# PowerBoard.net
KiCad netlist of a schematic drawn in EAGLE
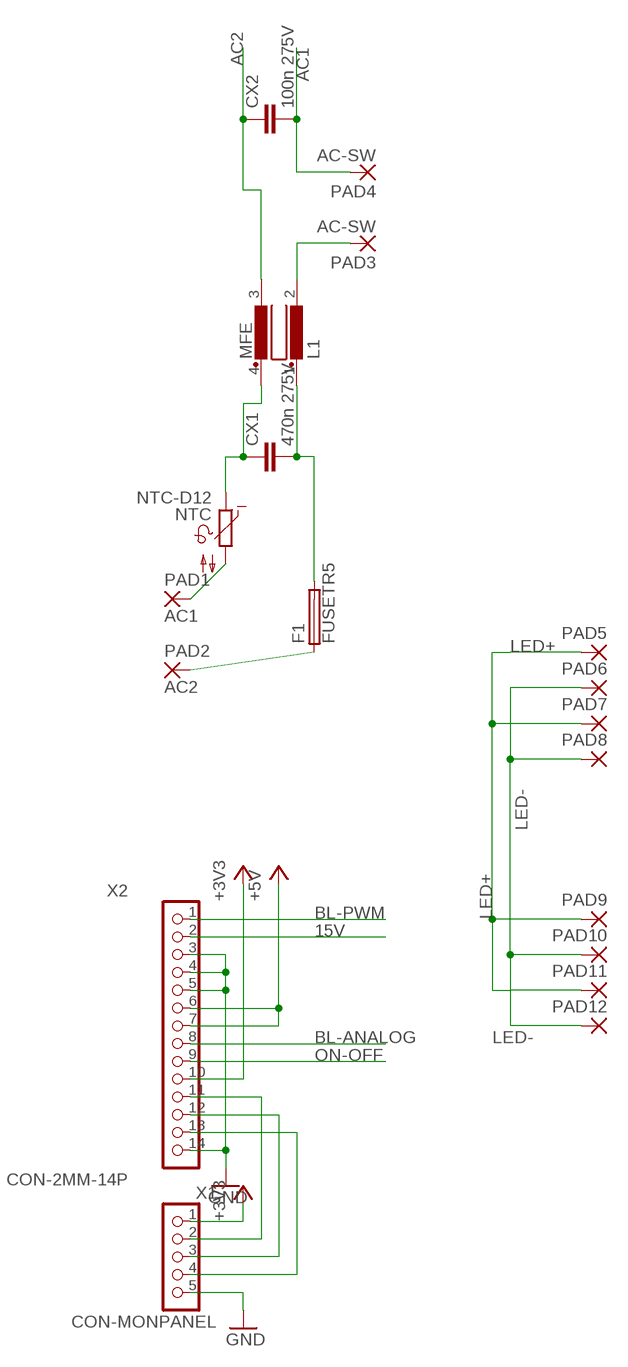
[diagram p0: schematic, sheet 1]
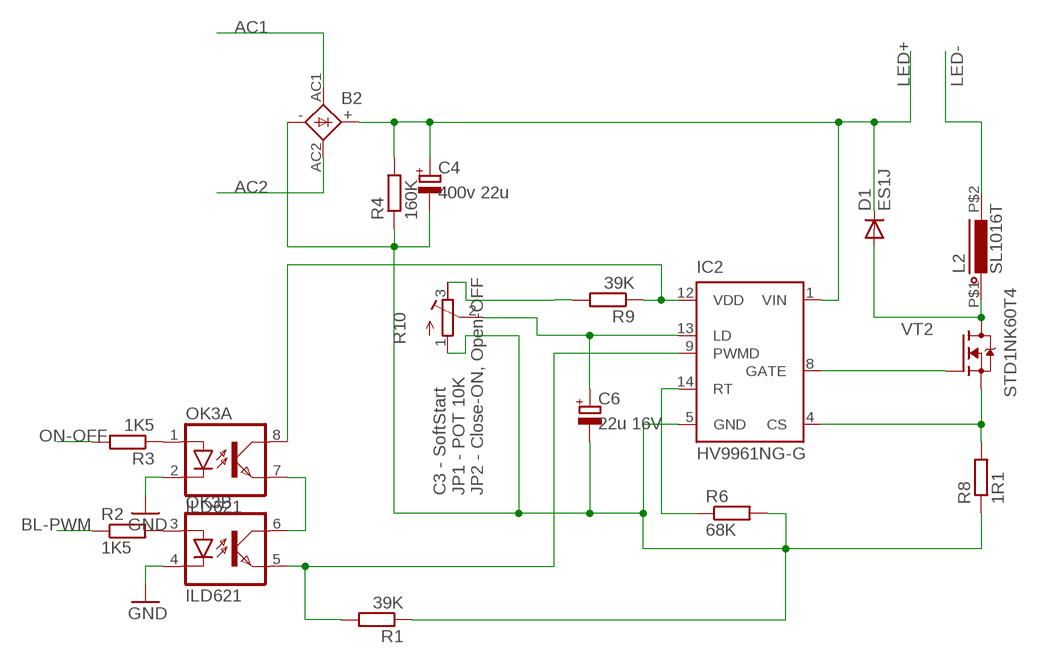
[diagram p1: schematic, sheet 2]
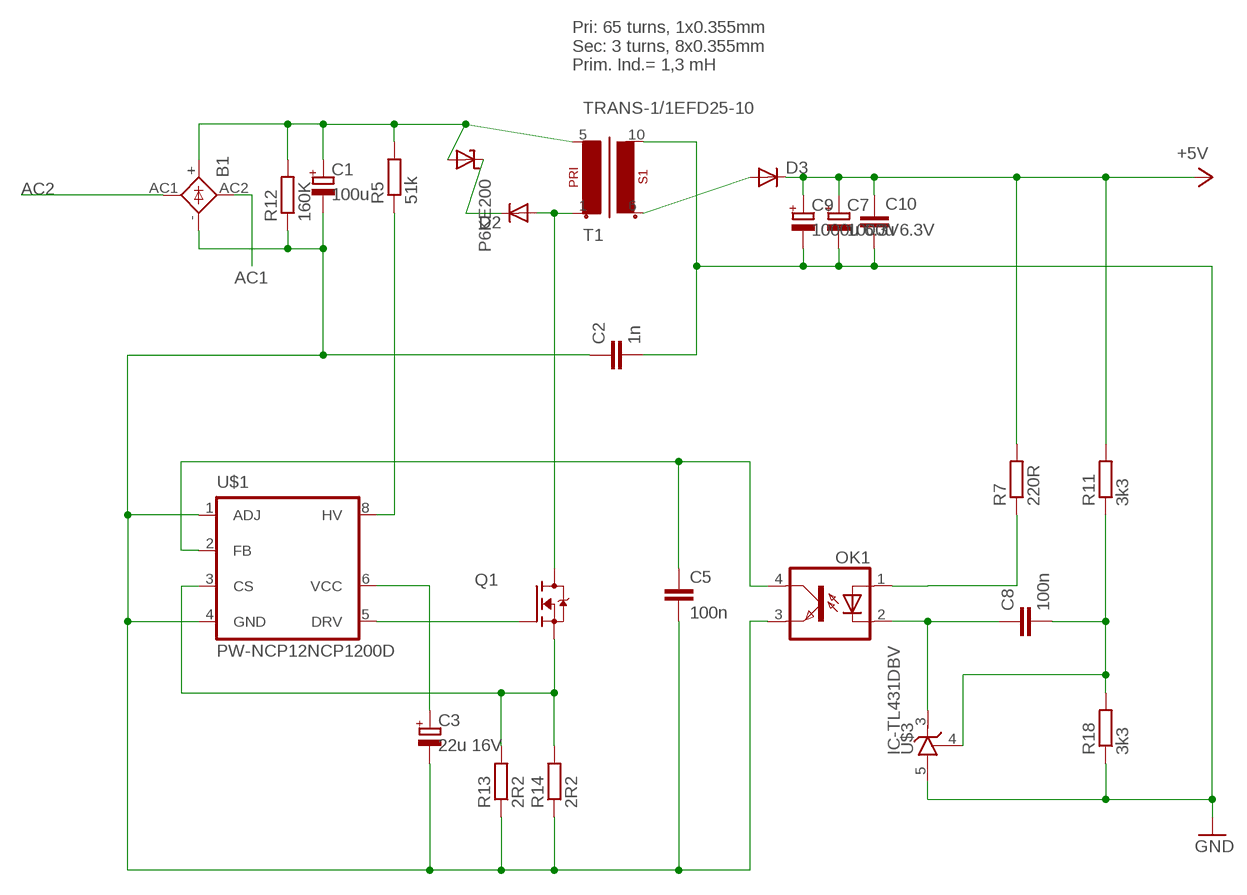
[diagram p2: schematic, sheet 3]

(export (version "E")
  (design (tool "Eeschema 10.0.6"))
  (components
    (comp (ref "B1")
      (value "KBL")
      (footprint "eagle-import:KBL")
      (libsource (lib "eagle-import") (part "KBL"))
    )
    (comp (ref "C1")
      (value "100u")
      (footprint "eagle-import:E5-13-35-HORIZ")
      (libsource (lib "eagle-import") (part "CAP-POL_E5-13-35-H"))
    )
    (comp (ref "C2")
      (value "1n")
      (footprint "eagle-import:C050-024X044")
      (libsource (lib "eagle-import") (part "Namenlos_CAP_C50-024X044"))
    )
    (comp (ref "C3")
      (value "22u 16V")
      (footprint "eagle-import:E2,5-7")
      (libsource (lib "eagle-import") (part "Namenlos_CAP-POL_E2.5-7"))
    )
    (comp (ref "C5")
      (value "100n")
      (footprint "eagle-import:CAP1206")
      (libsource (lib "eagle-import") (part "CAP_1206"))
    )
    (comp (ref "C7")
      (value "1000u 6.3V")
      (footprint "eagle-import:E3,5-8")
      (libsource (lib "eagle-import") (part "CAP-POL_E3.5-8"))
    )
    (comp (ref "C8")
      (value "100n")
      (footprint "eagle-import:CAP1206")
      (libsource (lib "eagle-import") (part "CAP_1206"))
    )
    (comp (ref "C9")
      (value "1000u 6.3V")
      (footprint "eagle-import:E3,5-8")
      (libsource (lib "eagle-import") (part "CAP-POL_E3.5-8"))
    )
    (comp (ref "C10")
      (value "CAP_0805")
      (footprint "eagle-import:CAP0805")
      (libsource (lib "eagle-import") (part "CAP_0805"))
    )
    (comp (ref "D2")
      (value "DIODE_ES1J")
      (footprint "eagle-import:DO214AC")
      (libsource (lib "eagle-import") (part "DIODE_ES1J"))
    )
    (comp (ref "D3")
      (value "DIODE_TO-220-2")
      (footprint "eagle-import:TO220ACS")
      (libsource (lib "eagle-import") (part "DIODE_TO-220-2"))
    )
    (comp (ref "OK1")
      (value "OPTOTRANSPC817")
      (footprint "eagle-import:DIL04")
      (fields (field (name "MPN") "PC817X4J000F"))
      (libsource (lib "eagle-import") (part "OPTOTRANSPC817"))
    )
    (comp (ref "P6KE200")
      (value "SUPRESSORDO-204AC")
      (footprint "eagle-import:DO15-12")
      (libsource (lib "eagle-import") (part "SUPRESSORDO-204AC"))
    )
    (comp (ref "Q1")
      (value "FET-NTO-220")
      (footprint "eagle-import:TO-220V")
      (libsource (lib "eagle-import") (part "FET-NTO-220"))
    )
    (comp (ref "R5")
      (value "51k")
      (footprint "eagle-import:SQP-5")
      (libsource (lib "eagle-import") (part "R_SQP-5"))
    )
    (comp (ref "R7")
      (value "220R")
      (footprint "eagle-import:RESC3216X60")
      (libsource (lib "eagle-import") (part "R_R1206"))
    )
    (comp (ref "R11")
      (value "3k3")
      (footprint "eagle-import:RESC3216X60")
      (libsource (lib "eagle-import") (part "R_R1206"))
    )
    (comp (ref "R12")
      (value "160K")
      (footprint "eagle-import:MF-0125")
      (libsource (lib "eagle-import") (part "Namenlos_R_MF-0125"))
    )
    (comp (ref "R13")
      (value "2R2")
      (footprint "eagle-import:MF-025")
      (libsource (lib "eagle-import") (part "R_MF-025"))
    )
    (comp (ref "R14")
      (value "2R2")
      (footprint "eagle-import:MF-025")
      (libsource (lib "eagle-import") (part "R_MF-025"))
    )
    (comp (ref "R18")
      (value "3k3")
      (footprint "eagle-import:RESC3216X60")
      (libsource (lib "eagle-import") (part "R_R1206"))
    )
    (comp (ref "T1")
      (value "TRANS-1/1EFD25-10")
      (footprint "eagle-import:EFD25_10PIN")
      (libsource (lib "eagle-import") (part "TRANS-1/1EFD25-10"))
    )
    (comp (ref "U$1")
      (value "PW-NCP12NCP1200D")
      (footprint "eagle-import:SO8")
      (libsource (lib "eagle-import") (part "PW-NCP12NCP1200D"))
    )
    (comp (ref "U$3")
      (value "IC-TL431DBV")
      (footprint "eagle-import:SOT95P280X145-5")
      (libsource (lib "eagle-import") (part "IC-TL431DBV"))
    )
    (comp (ref "CX1")
      (value "470n 275V")
      (footprint "eagle-import:XC15B10")
      (libsource (lib "eagle-import") (part "CXXC15B10"))
    )
    (comp (ref "CX2")
      (value "100n 275V")
      (footprint "eagle-import:XC15B6")
      (libsource (lib "eagle-import") (part "CXXC15B6"))
    )
    (comp (ref "F1")
      (value "FUSETR5")
      (footprint "eagle-import:TR5")
      (libsource (lib "eagle-import") (part "FUSETR5"))
    )
    (comp (ref "L1")
      (value "MFE")
      (footprint "eagle-import:MFE")
      (libsource (lib "eagle-import") (part "MFE"))
    )
    (comp (ref "NTC")
      (value "NTC-D12")
      (footprint "eagle-import:NTC-D12")
      (libsource (lib "eagle-import") (part "NTC-D12"))
    )
    (comp (ref "PAD1")
      (value "AC1")
      (footprint "eagle-import:3,81_1,4")
      (libsource (lib "eagle-import") (part "WIREPAD3,81/1,4"))
    )
    (comp (ref "PAD2")
      (value "AC2")
      (footprint "eagle-import:3,81_1,4")
      (libsource (lib "eagle-import") (part "WIREPAD3,81/1,4"))
    )
    (comp (ref "PAD3")
      (value "AC-SW")
      (footprint "eagle-import:2,54_1,1")
      (libsource (lib "eagle-import") (part "WIREPAD2,54/1,1"))
    )
    (comp (ref "PAD4")
      (value "AC-SW")
      (footprint "eagle-import:2,54_1,1")
      (libsource (lib "eagle-import") (part "WIREPAD2,54/1,1"))
    )
    (comp (ref "PAD5")
      (value "2,54/1,1")
      (footprint "eagle-import:2,54_1,1")
      (libsource (lib "eagle-import") (part "2,54/1,1"))
    )
    (comp (ref "PAD6")
      (value "2,54/1,1")
      (footprint "eagle-import:2,54_1,1")
      (libsource (lib "eagle-import") (part "2,54/1,1"))
    )
    (comp (ref "PAD7")
      (value "2,54/1,1")
      (footprint "eagle-import:2,54_1,1")
      (libsource (lib "eagle-import") (part "2,54/1,1"))
    )
    (comp (ref "PAD8")
      (value "2,54/1,1")
      (footprint "eagle-import:2,54_1,1")
      (libsource (lib "eagle-import") (part "2,54/1,1"))
    )
    (comp (ref "PAD9")
      (value "2,54/1,1")
      (footprint "eagle-import:2,54_1,1")
      (libsource (lib "eagle-import") (part "2,54/1,1"))
    )
    (comp (ref "PAD10")
      (value "2,54/1,1")
      (footprint "eagle-import:2,54_1,1")
      (libsource (lib "eagle-import") (part "2,54/1,1"))
    )
    (comp (ref "PAD11")
      (value "2,54/1,1")
      (footprint "eagle-import:2,54_1,1")
      (libsource (lib "eagle-import") (part "2,54/1,1"))
    )
    (comp (ref "PAD12")
      (value "2,54/1,1")
      (footprint "eagle-import:2,54_1,1")
      (libsource (lib "eagle-import") (part "2,54/1,1"))
    )
    (comp (ref "X1")
      (value "CON-MONPANEL")
      (footprint "eagle-import:CON-5-PANEL")
      (libsource (lib "eagle-import") (part "CON-MONPANEL"))
    )
    (comp (ref "X2")
      (value "CON-2MM-14P")
      (footprint "eagle-import:CON-14-2MM")
      (libsource (lib "eagle-import") (part "CON-2MM-14P"))
    )
    (comp (ref "B2")
      (value "BRIDGEDBS")
      (footprint "eagle-import:DBS")
      (libsource (lib "eagle-import") (part "BRIDGEDBS"))
    )
    (comp (ref "C4")
      (value "400v 22u")
      (footprint "eagle-import:E3,5-8")
      (libsource (lib "eagle-import") (part "Namenlos_CAP-POL_E3.5-8"))
    )
    (comp (ref "C6")
      (value "22u 16V")
      (footprint "eagle-import:CT3528")
      (libsource (lib "eagle-import") (part "CAP-POL_3528"))
    )
    (comp (ref "D1")
      (value "ES1J")
      (footprint "eagle-import:DO214AC")
      (libsource (lib "eagle-import") (part "DIODE_ES1J"))
    )
    (comp (ref "IC2")
      (value "HV9961NG-G")
      (footprint "eagle-import:SOIC-16NG")
      (libsource (lib "eagle-import") (part "HV9910BNG"))
    )
    (comp (ref "L2")
      (value "SL1016T")
      (footprint "eagle-import:SL1016")
      (libsource (lib "eagle-import") (part "INDUCTORSL1016"))
    )
    (comp (ref "OK3")
      (value "ILD621")
      (footprint "eagle-import:DIL08")
      (fields (field (name "MF") "VISHAY/TELEFUNKEN"))
      (libsource (lib "eagle-import") (part "ILD621"))
    )
    (comp (ref "R1")
      (value "39K")
      (footprint "eagle-import:RESC2012X50")
      (libsource (lib "eagle-import") (part "R_R0805"))
    )
    (comp (ref "R2")
      (value "1K5")
      (footprint "eagle-import:MF-025")
      (libsource (lib "eagle-import") (part "R_MF-025"))
    )
    (comp (ref "R3")
      (value "1K5")
      (footprint "eagle-import:MF-025")
      (libsource (lib "eagle-import") (part "R_MF-025"))
    )
    (comp (ref "R4")
      (value "160K")
      (footprint "eagle-import:MF-0125")
      (libsource (lib "eagle-import") (part "R_MF-0125"))
    )
    (comp (ref "R6")
      (value "68K")
      (footprint "eagle-import:RESC2012X50")
      (libsource (lib "eagle-import") (part "R_R0805"))
    )
    (comp (ref "R8")
      (value "1R1")
      (footprint "eagle-import:MF-05")
      (libsource (lib "eagle-import") (part "R_MF-05"))
    )
    (comp (ref "R9")
      (value "39K")
      (footprint "eagle-import:RESC2012X50")
      (libsource (lib "eagle-import") (part "R_R0805"))
    )
    (comp (ref "R10")
      (value "R_POT3296X")
      (footprint "eagle-import:POT-3296X")
      (libsource (lib "eagle-import") (part "R_POT3296X"))
    )
    (comp (ref "VT2")
      (value "STD1NK60T4")
      (footprint "eagle-import:DPAK")
      (libsource (lib "eagle-import") (part "FET-NDPAK"))
    )
  )
  (nets
    (net (code "1") (name "+3V3") (class "Default")
      (node (ref "X1") (pin "1") (pinfunction "1_1") (pintype "passive"))
      (node (ref "X2") (pin "10") (pinfunction "10_10") (pintype "passive"))
    )
    (net (code "2") (name "+5V") (class "Default")
      (node (ref "C10") (pin "1") (pinfunction "1_1") (pintype "passive"))
      (node (ref "C7") (pin "+") (pinfunction "+_+") (pintype "passive"))
      (node (ref "C9") (pin "+") (pinfunction "+_+") (pintype "passive"))
      (node (ref "D3") (pin "C") (pinfunction "C_C") (pintype "passive"))
      (node (ref "R11") (pin "2") (pinfunction "2_2") (pintype "passive"))
      (node (ref "R7") (pin "2") (pinfunction "2_2") (pintype "passive"))
      (node (ref "X2") (pin "6") (pinfunction "6_6") (pintype "passive"))
      (node (ref "X2") (pin "7") (pinfunction "7_7") (pintype "passive"))
    )
    (net (code "3") (name "15V") (class "Default")
      (node (ref "X2") (pin "2") (pinfunction "2_2") (pintype "passive"))
    )
    (net (code "4") (name "AC1") (class "Default")
      (node (ref "B1") (pin "AC2") (pinfunction "AC1_AC2") (pintype "passive"))
      (node (ref "B2") (pin "AC1") (pinfunction "AC1_AC1") (pintype "passive"))
      (node (ref "CX2") (pin "2") (pinfunction "2_2") (pintype "passive"))
      (node (ref "PAD4") (pin "1") (pinfunction "P_1") (pintype "passive"))
    )
    (net (code "5") (name "AC2") (class "Default")
      (node (ref "B1") (pin "AC1") (pinfunction "AC2_AC1") (pintype "passive"))
      (node (ref "B2") (pin "AC2") (pinfunction "AC2_AC2") (pintype "passive"))
      (node (ref "CX2") (pin "1") (pinfunction "1_1") (pintype "passive"))
      (node (ref "L1") (pin "3") (pinfunction "4_3") (pintype "passive"))
    )
    (net (code "6") (name "BL-ANALOG") (class "Default")
      (node (ref "X2") (pin "8") (pinfunction "8_8") (pintype "passive"))
    )
    (net (code "7") (name "BL-PWM") (class "Default")
      (node (ref "R2") (pin "1") (pinfunction "1_1") (pintype "passive"))
      (node (ref "X2") (pin "1") (pinfunction "1_1") (pintype "passive"))
    )
    (net (code "8") (name "GND") (class "Default")
      (node (ref "C10") (pin "2") (pinfunction "2_2") (pintype "passive"))
      (node (ref "C2") (pin "2") (pinfunction "2_2") (pintype "passive"))
      (node (ref "C7") (pin "-") (pinfunction "-_-") (pintype "passive"))
      (node (ref "C9") (pin "-") (pinfunction "-_-") (pintype "passive"))
      (node (ref "OK3") (pin "2") (pinfunction "C_2") (pintype "passive"))
      (node (ref "OK3") (pin "4") (pinfunction "C_4") (pintype "passive"))
      (node (ref "R18") (pin "1") (pinfunction "1_1") (pintype "passive"))
      (node (ref "T1") (pin "10") (pinfunction "S1-2_10") (pintype "passive"))
      (node (ref "U$3") (pin "5") (pinfunction "A_5") (pintype "passive"))
      (node (ref "X1") (pin "5") (pinfunction "5_5") (pintype "passive"))
      (node (ref "X2") (pin "14") (pinfunction "14_14") (pintype "passive"))
      (node (ref "X2") (pin "3") (pinfunction "3_3") (pintype "passive"))
      (node (ref "X2") (pin "4") (pinfunction "4_4") (pintype "passive"))
      (node (ref "X2") (pin "5") (pinfunction "5_5") (pintype "passive"))
    )
    (net (code "9") (name "LED+") (class "Default")
      (node (ref "B2") (pin "+") (pinfunction "+_+") (pintype "passive"))
      (node (ref "C4") (pin "+") (pinfunction "+_+") (pintype "passive"))
      (node (ref "D1") (pin "C") (pinfunction "C_C") (pintype "passive"))
      (node (ref "IC2") (pin "1") (pinfunction "VIN_1") (pintype "input"))
      (node (ref "PAD11") (pin "1") (pinfunction "P_1") (pintype "passive"))
      (node (ref "PAD5") (pin "1") (pinfunction "P_1") (pintype "passive"))
      (node (ref "PAD7") (pin "1") (pinfunction "P_1") (pintype "passive"))
      (node (ref "PAD9") (pin "1") (pinfunction "P_1") (pintype "passive"))
      (node (ref "R4") (pin "2") (pinfunction "2_2") (pintype "passive"))
    )
    (net (code "10") (name "LED-") (class "Default")
      (node (ref "L2") (pin "P$2") (pinfunction "2_P$2") (pintype "passive"))
      (node (ref "PAD10") (pin "1") (pinfunction "P_1") (pintype "passive"))
      (node (ref "PAD12") (pin "1") (pinfunction "P_1") (pintype "passive"))
      (node (ref "PAD6") (pin "1") (pinfunction "P_1") (pintype "passive"))
      (node (ref "PAD8") (pin "1") (pinfunction "P_1") (pintype "passive"))
    )
    (net (code "11") (name "Net-(CX1-Pad2)") (class "Default")
      (node (ref "CX1") (pin "2") (pinfunction "2_2") (pintype "passive"))
      (node (ref "F1") (pin "2") (pinfunction "2_2") (pintype "passive"))
      (node (ref "L1") (pin "1") (pinfunction "1_1") (pintype "passive"))
    )
    (net (code "12") (name "Net-(D2-PadC)") (class "Default")
      (node (ref "D2") (pin "C") (pinfunction "C_C") (pintype "passive"))
      (node (ref "P6KE200") (pin "C") (pinfunction "C_C") (pintype "passive"))
    )
    (net (code "13") (name "Net-(IC2-CS)") (class "Default")
      (node (ref "IC2") (pin "4") (pinfunction "CS_4") (pintype "input"))
      (node (ref "R8") (pin "2") (pinfunction "2_2") (pintype "passive"))
      (node (ref "VT2") (pin "S") (pinfunction "S_S") (pintype "passive"))
    )
    (net (code "14") (name "Net-(IC2-GATE)") (class "Default")
      (node (ref "IC2") (pin "8") (pinfunction "GATE_8") (pintype "output"))
      (node (ref "VT2") (pin "G") (pinfunction "G_G") (pintype "passive"))
    )
    (net (code "15") (name "Net-(IC2-GND)") (class "Default")
      (node (ref "B2") (pin "-") (pinfunction "-_-") (pintype "passive"))
      (node (ref "C4") (pin "-") (pinfunction "-_-") (pintype "passive"))
      (node (ref "C6") (pin "-") (pinfunction "-_-") (pintype "passive"))
      (node (ref "IC2") (pin "5") (pinfunction "GND_5") (pintype "power_in"))
      (node (ref "R1") (pin "1") (pinfunction "1_1") (pintype "passive"))
      (node (ref "R10") (pin "1") (pinfunction "A_1") (pintype "passive"))
      (node (ref "R4") (pin "1") (pinfunction "1_1") (pintype "passive"))
      (node (ref "R6") (pin "2") (pinfunction "2_2") (pintype "passive"))
      (node (ref "R8") (pin "1") (pinfunction "1_1") (pintype "passive"))
    )
    (net (code "16") (name "Net-(IC2-LD)") (class "Default")
      (node (ref "C6") (pin "+") (pinfunction "+_+") (pintype "passive"))
      (node (ref "IC2") (pin "13") (pinfunction "LD_13") (pintype "input"))
      (node (ref "R10") (pin "2") (pinfunction "S_2") (pintype "passive"))
    )
    (net (code "17") (name "Net-(IC2-PWMD)") (class "Default")
      (node (ref "IC2") (pin "9") (pinfunction "PWMD_9") (pintype "input"))
      (node (ref "OK3") (pin "5") (pinfunction "EMIT_5") (pintype "passive"))
      (node (ref "R1") (pin "2") (pinfunction "2_2") (pintype "passive"))
    )
    (net (code "18") (name "Net-(IC2-RT)") (class "Default")
      (node (ref "IC2") (pin "14") (pinfunction "RT_14") (pintype "passive"))
      (node (ref "R6") (pin "1") (pinfunction "1_1") (pintype "passive"))
    )
    (net (code "19") (name "Net-(IC2-VDD)") (class "Default")
      (node (ref "IC2") (pin "12") (pinfunction "VDD_12") (pintype "power_in"))
      (node (ref "OK3") (pin "8") (pinfunction "COL_8") (pintype "passive"))
      (node (ref "R9") (pin "1") (pinfunction "1_1") (pintype "passive"))
    )
    (net (code "20") (name "Net-(L1-3)") (class "Default")
      (node (ref "CX1") (pin "1") (pinfunction "1_1") (pintype "passive"))
      (node (ref "L1") (pin "4") (pinfunction "3_4") (pintype "passive"))
      (node (ref "NTC") (pin "1") (pinfunction "1_1") (pintype "passive"))
    )
    (net (code "21") (name "Net-(L2-1)") (class "Default")
      (node (ref "D1") (pin "A") (pinfunction "A_A") (pintype "passive"))
      (node (ref "L2") (pin "P$1") (pinfunction "1_P$1") (pintype "passive"))
      (node (ref "VT2") (pin "D") (pinfunction "D_D") (pintype "passive"))
    )
    (net (code "22") (name "Net-(OK1-A)") (class "Default")
      (node (ref "OK1") (pin "1") (pinfunction "A_1") (pintype "passive"))
      (node (ref "R7") (pin "1") (pinfunction "1_1") (pintype "passive"))
    )
    (net (code "23") (name "Net-(OK1-C)") (class "Default")
      (node (ref "C8") (pin "1") (pinfunction "1_1") (pintype "passive"))
      (node (ref "OK1") (pin "2") (pinfunction "C_2") (pintype "passive"))
      (node (ref "U$3") (pin "3") (pinfunction "C_3") (pintype "passive"))
    )
    (net (code "24") (name "Net-(OK1-COL)") (class "Default")
      (node (ref "C5") (pin "1") (pinfunction "1_1") (pintype "passive"))
      (node (ref "OK1") (pin "4") (pinfunction "COL_4") (pintype "passive"))
      (node (ref "U$1") (pin "2") (pinfunction "FB_2") (pintype "input"))
    )
    (net (code "25") (name "Net-(OK1-EMIT)") (class "Default")
      (node (ref "B1") (pin "-") (pinfunction "-_-") (pintype "passive"))
      (node (ref "C1") (pin "-") (pinfunction "-_-") (pintype "passive"))
      (node (ref "C2") (pin "1") (pinfunction "1_1") (pintype "passive"))
      (node (ref "C3") (pin "-") (pinfunction "-_-") (pintype "passive"))
      (node (ref "C5") (pin "2") (pinfunction "2_2") (pintype "passive"))
      (node (ref "OK1") (pin "3") (pinfunction "EMIT_3") (pintype "passive"))
      (node (ref "R12") (pin "1") (pinfunction "1_1") (pintype "passive"))
      (node (ref "R13") (pin "1") (pinfunction "1_1") (pintype "passive"))
      (node (ref "R14") (pin "1") (pinfunction "1_1") (pintype "passive"))
      (node (ref "U$1") (pin "1") (pinfunction "ADJ_1") (pintype "passive"))
      (node (ref "U$1") (pin "4") (pinfunction "GND_4") (pintype "passive"))
    )
    (net (code "26") (name "Net-(OK3A-A)") (class "Default")
      (node (ref "OK3") (pin "1") (pinfunction "A_1") (pintype "passive"))
      (node (ref "R3") (pin "1") (pinfunction "1_1") (pintype "passive"))
    )
    (net (code "27") (name "Net-(OK3A-EMIT)") (class "Default")
      (node (ref "OK3") (pin "6") (pinfunction "COL_6") (pintype "passive"))
      (node (ref "OK3") (pin "7") (pinfunction "EMIT_7") (pintype "passive"))
    )
    (net (code "28") (name "Net-(OK3B-A)") (class "Default")
      (node (ref "OK3") (pin "3") (pinfunction "A_3") (pintype "passive"))
      (node (ref "R2") (pin "2") (pinfunction "2_2") (pintype "passive"))
    )
    (net (code "29") (name "Net-(PAD1-P)") (class "Default")
      (node (ref "NTC") (pin "2") (pinfunction "2_2") (pintype "passive"))
      (node (ref "PAD1") (pin "1") (pinfunction "P_1") (pintype "passive"))
    )
    (net (code "30") (name "Net-(PAD2-P)") (class "Default")
      (node (ref "F1") (pin "1") (pinfunction "1_1") (pintype "passive"))
      (node (ref "PAD2") (pin "1") (pinfunction "P_1") (pintype "passive"))
    )
    (net (code "31") (name "Net-(PAD3-P)") (class "Default")
      (node (ref "L1") (pin "2") (pinfunction "2_2") (pintype "passive"))
      (node (ref "PAD3") (pin "1") (pinfunction "P_1") (pintype "passive"))
    )
    (net (code "32") (name "Net-(Q1-D)") (class "Default")
      (node (ref "D2") (pin "A") (pinfunction "A_A") (pintype "passive"))
      (node (ref "Q1") (pin "2") (pinfunction "D_2") (pintype "passive"))
      (node (ref "T1") (pin "1") (pinfunction "P1-1_1") (pintype "passive"))
    )
    (net (code "33") (name "Net-(Q1-G)") (class "Default")
      (node (ref "Q1") (pin "1") (pinfunction "G_1") (pintype "passive"))
      (node (ref "U$1") (pin "5") (pinfunction "DRV_5") (pintype "power_in"))
    )
    (net (code "34") (name "Net-(Q1-S)") (class "Default")
      (node (ref "Q1") (pin "3") (pinfunction "S_3") (pintype "passive"))
      (node (ref "R13") (pin "2") (pinfunction "2_2") (pintype "passive"))
      (node (ref "R14") (pin "2") (pinfunction "2_2") (pintype "passive"))
      (node (ref "U$1") (pin "3") (pinfunction "CS_3") (pintype "input"))
    )
    (net (code "35") (name "Net-(R10-E)") (class "Default")
      (node (ref "R10") (pin "3") (pinfunction "E_3") (pintype "passive"))
      (node (ref "R9") (pin "2") (pinfunction "2_2") (pintype "passive"))
    )
    (net (code "36") (name "Net-(T1-P1-2)") (class "Default")
      (node (ref "B1") (pin "+") (pinfunction "+_+") (pintype "passive"))
      (node (ref "C1") (pin "+") (pinfunction "+_+") (pintype "passive"))
      (node (ref "P6KE200") (pin "A") (pinfunction "A_A") (pintype "passive"))
      (node (ref "R12") (pin "2") (pinfunction "2_2") (pintype "passive"))
      (node (ref "R5") (pin "2") (pinfunction "2_2") (pintype "passive"))
      (node (ref "T1") (pin "5") (pinfunction "P1-2_5") (pintype "passive"))
    )
    (net (code "37") (name "Net-(T1-S1-1)") (class "Default")
      (node (ref "D3") (pin "A") (pinfunction "A_A") (pintype "passive"))
      (node (ref "T1") (pin "6") (pinfunction "S1-1_6") (pintype "passive"))
    )
    (net (code "38") (name "Net-(U$1-HV)") (class "Default")
      (node (ref "R5") (pin "1") (pinfunction "1_1") (pintype "passive"))
      (node (ref "U$1") (pin "8") (pinfunction "HV_8") (pintype "passive"))
    )
    (net (code "39") (name "Net-(U$1-VCC)") (class "Default")
      (node (ref "C3") (pin "+") (pinfunction "+_+") (pintype "passive"))
      (node (ref "U$1") (pin "6") (pinfunction "VCC_6") (pintype "output"))
    )
    (net (code "40") (name "Net-(U$3-R)") (class "Default")
      (node (ref "C8") (pin "2") (pinfunction "2_2") (pintype "passive"))
      (node (ref "R11") (pin "1") (pinfunction "1_1") (pintype "passive"))
      (node (ref "R18") (pin "2") (pinfunction "2_2") (pintype "passive"))
      (node (ref "U$3") (pin "4") (pinfunction "R_4") (pintype "passive"))
    )
    (net (code "41") (name "Net-(X1-Pad2)") (class "Default")
      (node (ref "X1") (pin "2") (pinfunction "2_2") (pintype "passive"))
      (node (ref "X2") (pin "11") (pinfunction "11_11") (pintype "passive"))
    )
    (net (code "42") (name "Net-(X1-Pad3)") (class "Default")
      (node (ref "X1") (pin "3") (pinfunction "3_3") (pintype "passive"))
      (node (ref "X2") (pin "12") (pinfunction "12_12") (pintype "passive"))
    )
    (net (code "43") (name "Net-(X1-Pad4)") (class "Default")
      (node (ref "X1") (pin "4") (pinfunction "4_4") (pintype "passive"))
      (node (ref "X2") (pin "13") (pinfunction "13_13") (pintype "passive"))
    )
    (net (code "44") (name "ON-OFF") (class "Default")
      (node (ref "R3") (pin "2") (pinfunction "2_2") (pintype "passive"))
      (node (ref "X2") (pin "9") (pinfunction "9_9") (pintype "passive"))
    )
  )
)
